# main-board.net
KiCad netlist of a schematic drawn in EAGLE
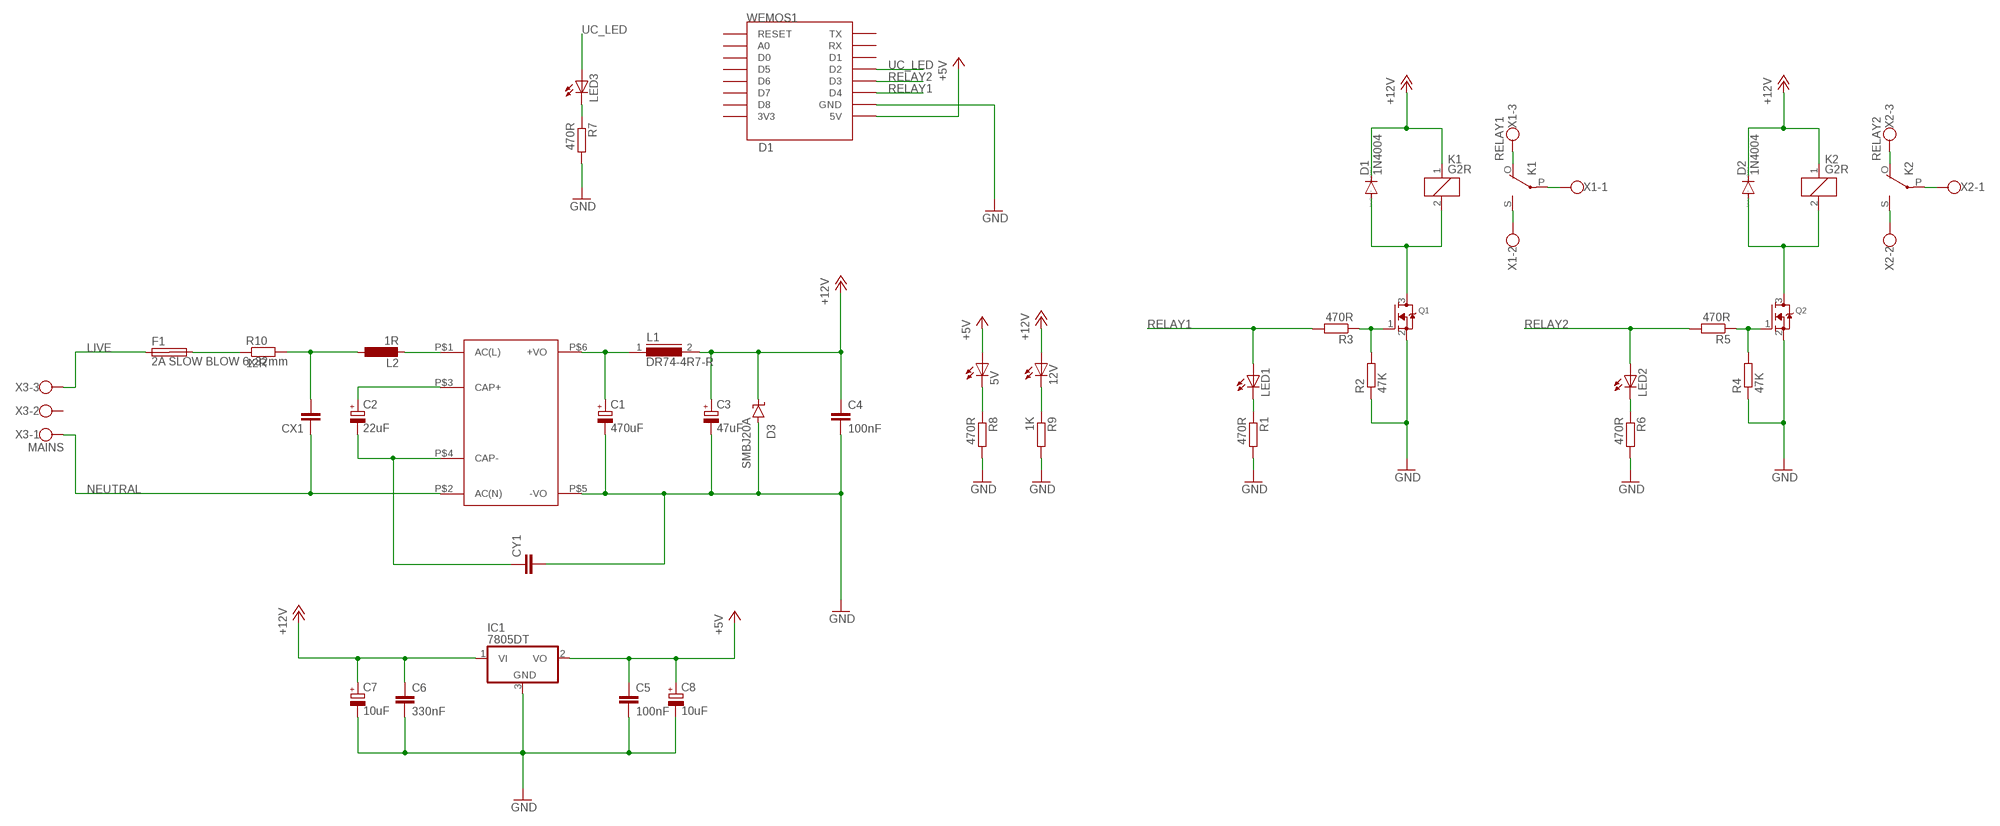
[diagram p0: schematic, sheet 1]

(export (version "E")
  (design (tool "Eeschema 10.0.6"))
  (components
    (comp (ref "5V")
      (value "LEDSMT1206")
      (footprint "eagle-import:1206")
      (libsource (lib "eagle-import") (part "LEDSMT1206"))
    )
    (comp (ref "12V")
      (value "LEDSMT1206")
      (footprint "eagle-import:1206")
      (libsource (lib "eagle-import") (part "LEDSMT1206"))
    )
    (comp (ref "C1")
      (value "470uF")
      (footprint "eagle-import:PANASONIC_E")
      (libsource (lib "eagle-import") (part "CPOL-EUE"))
    )
    (comp (ref "C2")
      (value "22uF")
      (footprint "eagle-import:E7,5-16")
      (libsource (lib "eagle-import") (part "CPOL-EUE7.5-16"))
    )
    (comp (ref "C3")
      (value "47uF")
      (footprint "eagle-import:PANASONIC_D")
      (libsource (lib "eagle-import") (part "CPOL-EUD"))
    )
    (comp (ref "C4")
      (value "100nF")
      (footprint "eagle-import:C0603")
      (libsource (lib "eagle-import") (part "C-EUC0603"))
    )
    (comp (ref "C5")
      (value "100nF")
      (footprint "eagle-import:C0603")
      (libsource (lib "eagle-import") (part "C-EUC0603"))
    )
    (comp (ref "C6")
      (value "330nF")
      (footprint "eagle-import:C0603")
      (libsource (lib "eagle-import") (part "C-EUC0603"))
    )
    (comp (ref "C7")
      (value "10uF")
      (footprint "eagle-import:PANASONIC_B")
      (libsource (lib "eagle-import") (part "CPOL-EUB"))
    )
    (comp (ref "C8")
      (value "10uF")
      (footprint "eagle-import:PANASONIC_B")
      (libsource (lib "eagle-import") (part "CPOL-EUB"))
    )
    (comp (ref "CX1")
      (value "CXXC15B8")
      (footprint "eagle-import:XC15B8")
      (libsource (lib "eagle-import") (part "CXXC15B8"))
    )
    (comp (ref "CY1")
      (value "CYYC10B5")
      (footprint "eagle-import:YC10B5")
      (libsource (lib "eagle-import") (part "CYYC10B5"))
    )
    (comp (ref "D1")
      (value "1N4004")
      (footprint "eagle-import:DO41-10")
      (libsource (lib "eagle-import") (part "1N4004"))
    )
    (comp (ref "D2")
      (value "1N4004")
      (footprint "eagle-import:DO41-10")
      (libsource (lib "eagle-import") (part "1N4004"))
    )
    (comp (ref "D3")
      (value "SMBJ20A")
      (footprint "eagle-import:SMBJ")
      (libsource (lib "eagle-import") (part "SUPPRESSOR-SMBJ"))
    )
    (comp (ref "F1")
      (value "2A SLOW BLOW 6x32mm")
      (footprint "eagle-import:SH32")
      (fields (field (name "MPN") "10207101009"))
      (libsource (lib "eagle-import") (part "SH32"))
    )
    (comp (ref "IC1")
      (value "7805DT")
      (footprint "eagle-import:TO252")
      (libsource (lib "eagle-import") (part "78DT05"))
    )
    (comp (ref "K1")
      (value "G2R")
      (footprint "eagle-import:G2R")
      (libsource (lib "eagle-import") (part "G2R"))
    )
    (comp (ref "K2")
      (value "G2R")
      (footprint "eagle-import:G2R")
      (libsource (lib "eagle-import") (part "G2R"))
    )
    (comp (ref "L1")
      (value "DR74-4R7-R")
      (footprint "eagle-import:DR74")
      (libsource (lib "eagle-import") (part "DR74"))
    )
    (comp (ref "L2")
      (value "1R")
      (footprint "eagle-import:6000-XXXX-RC")
      (libsource (lib "eagle-import") (part "L-EU6000-XXX-RC"))
    )
    (comp (ref "LED1")
      (value "LEDSMT1206")
      (footprint "eagle-import:1206")
      (libsource (lib "eagle-import") (part "LEDSMT1206"))
    )
    (comp (ref "LED2")
      (value "LEDSMT1206")
      (footprint "eagle-import:1206")
      (libsource (lib "eagle-import") (part "LEDSMT1206"))
    )
    (comp (ref "LED3")
      (value "LEDSMT1206")
      (footprint "eagle-import:1206")
      (libsource (lib "eagle-import") (part "LEDSMT1206"))
    )
    (comp (ref "Q1")
      (value "MOSFET-NREFLOW")
      (footprint "eagle-import:SOT23")
      (libsource (lib "eagle-import") (part "MOSFET-NREFLOW"))
    )
    (comp (ref "Q2")
      (value "MOSFET-NREFLOW")
      (footprint "eagle-import:SOT23")
      (libsource (lib "eagle-import") (part "MOSFET-NREFLOW"))
    )
    (comp (ref "R1")
      (value "470R")
      (footprint "eagle-import:R0603")
      (libsource (lib "eagle-import") (part "R-EU_R0603"))
    )
    (comp (ref "R2")
      (value "47K")
      (footprint "eagle-import:R0603")
      (libsource (lib "eagle-import") (part "R-EU_R0603"))
    )
    (comp (ref "R3")
      (value "470R")
      (footprint "eagle-import:R0603")
      (libsource (lib "eagle-import") (part "R-EU_R0603"))
    )
    (comp (ref "R4")
      (value "47K")
      (footprint "eagle-import:R0603")
      (libsource (lib "eagle-import") (part "R-EU_R0603"))
    )
    (comp (ref "R5")
      (value "470R")
      (footprint "eagle-import:R0603")
      (libsource (lib "eagle-import") (part "R-EU_R0603"))
    )
    (comp (ref "R6")
      (value "470R")
      (footprint "eagle-import:R0603")
      (libsource (lib "eagle-import") (part "R-EU_R0603"))
    )
    (comp (ref "R7")
      (value "470R")
      (footprint "eagle-import:R0603")
      (libsource (lib "eagle-import") (part "R-EU_R0603"))
    )
    (comp (ref "R8")
      (value "470R")
      (footprint "eagle-import:R0603")
      (libsource (lib "eagle-import") (part "R-EU_R0603"))
    )
    (comp (ref "R9")
      (value "1K")
      (footprint "eagle-import:R0603")
      (libsource (lib "eagle-import") (part "R-EU_R0603"))
    )
    (comp (ref "R10")
      (value "12R")
      (footprint "eagle-import:0922V")
      (libsource (lib "eagle-import") (part "R-EU_0922V"))
    )
    (comp (ref "U$1")
      (value "MP-LS05")
      (footprint "eagle-import:MP-LS05")
      (libsource (lib "eagle-import") (part "MP-LS05"))
    )
    (comp (ref "WEMOS1")
      (value "D1")
      (footprint "eagle-import:WEMOS-D1-MINI")
      (libsource (lib "eagle-import") (part "WEMOS-D1-MINI"))
    )
    (comp (ref "X1")
      (value "RELAY1")
      (footprint "eagle-import:W237-103")
      (fields (field (name "MPN") "237-103"))
      (libsource (lib "eagle-import") (part "W237-103"))
    )
    (comp (ref "X2")
      (value "RELAY2")
      (footprint "eagle-import:W237-103")
      (fields (field (name "MPN") "237-103"))
      (libsource (lib "eagle-import") (part "W237-103"))
    )
    (comp (ref "X3")
      (value "MAINS")
      (footprint "eagle-import:W237-103")
      (fields (field (name "MPN") "237-103"))
      (libsource (lib "eagle-import") (part "W237-103"))
    )
  )
  (nets
    (net (code "1") (name "+5V") (class "Default")
      (node (ref "5V") (pin "A") (pinfunction "A_A") (pintype "passive"))
      (node (ref "C5") (pin "1") (pinfunction "1_1") (pintype "passive"))
      (node (ref "C8") (pin "+") (pinfunction "+_+") (pintype "passive"))
      (node (ref "IC1") (pin "2") (pinfunction "VO_2") (pintype "passive"))
      (node (ref "WEMOS1") (pin "5V") (pinfunction "5V_5V") (pintype "bidirectional"))
    )
    (net (code "2") (name "+12V") (class "Default")
      (node (ref "12V") (pin "A") (pinfunction "A_A") (pintype "passive"))
      (node (ref "C3") (pin "+") (pinfunction "+_+") (pintype "passive"))
      (node (ref "C4") (pin "1") (pinfunction "1_1") (pintype "passive"))
      (node (ref "C6") (pin "1") (pinfunction "1_1") (pintype "passive"))
      (node (ref "C7") (pin "+") (pinfunction "+_+") (pintype "passive"))
      (node (ref "D1") (pin "C") (pinfunction "C_C") (pintype "passive"))
      (node (ref "D2") (pin "C") (pinfunction "C_C") (pintype "passive"))
      (node (ref "D3") (pin "C") (pinfunction "C_C") (pintype "passive"))
      (node (ref "IC1") (pin "1") (pinfunction "VI_1") (pintype "input"))
      (node (ref "K1") (pin "1") (pinfunction "1_1") (pintype "passive"))
      (node (ref "K2") (pin "1") (pinfunction "1_1") (pintype "passive"))
      (node (ref "L1") (pin "2") (pinfunction "2_2") (pintype "passive"))
    )
    (net (code "3") (name "/LIVE") (class "Default")
      (node (ref "F1") (pin "1A") (pinfunction "1A_1A") (pintype "passive"))
      (node (ref "X3") (pin "3") (pinfunction "KL_3") (pintype "passive"))
    )
    (net (code "4") (name "/NEUTRAL") (class "Default")
      (node (ref "CX1") (pin "1") (pinfunction "1_1") (pintype "passive"))
      (node (ref "U$1") (pin "P$2") (pinfunction "AC(N)_P$2") (pintype "bidirectional"))
      (node (ref "X3") (pin "1") (pinfunction "KL_1") (pintype "passive"))
    )
    (net (code "5") (name "/RELAY1") (class "Default")
      (node (ref "LED1") (pin "A") (pinfunction "A_A") (pintype "passive"))
      (node (ref "R3") (pin "2") (pinfunction "2_2") (pintype "passive"))
      (node (ref "WEMOS1") (pin "D4") (pinfunction "D4_D4") (pintype "bidirectional"))
    )
    (net (code "6") (name "/RELAY2") (class "Default")
      (node (ref "LED2") (pin "A") (pinfunction "A_A") (pintype "passive"))
      (node (ref "R5") (pin "2") (pinfunction "2_2") (pintype "passive"))
      (node (ref "WEMOS1") (pin "D3") (pinfunction "D3_D3") (pintype "bidirectional"))
    )
    (net (code "7") (name "/UC_LED") (class "Default")
      (node (ref "LED3") (pin "A") (pinfunction "A_A") (pintype "passive"))
      (node (ref "WEMOS1") (pin "D2") (pinfunction "D2_D2") (pintype "bidirectional"))
    )
    (net (code "8") (name "GND") (class "Default")
      (node (ref "C1") (pin "-") (pinfunction "-_-") (pintype "passive"))
      (node (ref "C3") (pin "-") (pinfunction "-_-") (pintype "passive"))
      (node (ref "C4") (pin "2") (pinfunction "2_2") (pintype "passive"))
      (node (ref "C5") (pin "2") (pinfunction "2_2") (pintype "passive"))
      (node (ref "C6") (pin "2") (pinfunction "2_2") (pintype "passive"))
      (node (ref "C7") (pin "-") (pinfunction "-_-") (pintype "passive"))
      (node (ref "C8") (pin "-") (pinfunction "-_-") (pintype "passive"))
      (node (ref "CY1") (pin "2") (pinfunction "2_2") (pintype "passive"))
      (node (ref "D3") (pin "A") (pinfunction "A_A") (pintype "passive"))
      (node (ref "IC1") (pin "3") (pinfunction "GND_3") (pintype "passive"))
      (node (ref "Q1") (pin "2") (pinfunction "S_2") (pintype "bidirectional"))
      (node (ref "Q2") (pin "2") (pinfunction "S_2") (pintype "bidirectional"))
      (node (ref "R1") (pin "2") (pinfunction "2_2") (pintype "passive"))
      (node (ref "R2") (pin "1") (pinfunction "1_1") (pintype "passive"))
      (node (ref "R4") (pin "1") (pinfunction "1_1") (pintype "passive"))
      (node (ref "R6") (pin "2") (pinfunction "2_2") (pintype "passive"))
      (node (ref "R7") (pin "2") (pinfunction "2_2") (pintype "passive"))
      (node (ref "R8") (pin "2") (pinfunction "2_2") (pintype "passive"))
      (node (ref "R9") (pin "2") (pinfunction "2_2") (pintype "passive"))
      (node (ref "U$1") (pin "P$5") (pinfunction "-VO_P$5") (pintype "bidirectional"))
      (node (ref "WEMOS1") (pin "GND") (pinfunction "GND_GND") (pintype "bidirectional"))
    )
    (net (code "9") (name "Net-(5V-PadC)") (class "Default")
      (node (ref "5V") (pin "C") (pinfunction "C_C") (pintype "passive"))
      (node (ref "R8") (pin "1") (pinfunction "1_1") (pintype "passive"))
    )
    (net (code "10") (name "Net-(12V-PadC)") (class "Default")
      (node (ref "12V") (pin "C") (pinfunction "C_C") (pintype "passive"))
      (node (ref "R9") (pin "1") (pinfunction "1_1") (pintype "passive"))
    )
    (net (code "11") (name "Net-(CX1-Pad2)") (class "Default")
      (node (ref "CX1") (pin "2") (pinfunction "2_2") (pintype "passive"))
      (node (ref "L2") (pin "1") (pinfunction "1_1") (pintype "passive"))
      (node (ref "R10") (pin "2") (pinfunction "2_2") (pintype "passive"))
    )
    (net (code "12") (name "Net-(F1-Pad2A)") (class "Default")
      (node (ref "F1") (pin "2A") (pinfunction "2A_2A") (pintype "passive"))
      (node (ref "R10") (pin "1") (pinfunction "1_1") (pintype "passive"))
    )
    (net (code "13") (name "Net-(LED1-PadC)") (class "Default")
      (node (ref "LED1") (pin "C") (pinfunction "C_C") (pintype "passive"))
      (node (ref "R1") (pin "1") (pinfunction "1_1") (pintype "passive"))
    )
    (net (code "14") (name "Net-(LED2-PadC)") (class "Default")
      (node (ref "LED2") (pin "C") (pinfunction "C_C") (pintype "passive"))
      (node (ref "R6") (pin "1") (pinfunction "1_1") (pintype "passive"))
    )
    (net (code "15") (name "Net-(LED3-PadC)") (class "Default")
      (node (ref "LED3") (pin "C") (pinfunction "C_C") (pintype "passive"))
      (node (ref "R7") (pin "1") (pinfunction "1_1") (pintype "passive"))
    )
    (net (code "16") (name "Net-(Q1-D)") (class "Default")
      (node (ref "D1") (pin "A") (pinfunction "A_A") (pintype "passive"))
      (node (ref "K1") (pin "2") (pinfunction "2_2") (pintype "passive"))
      (node (ref "Q1") (pin "3") (pinfunction "D_3") (pintype "bidirectional"))
    )
    (net (code "17") (name "Net-(Q1-G)") (class "Default")
      (node (ref "Q1") (pin "1") (pinfunction "G_1") (pintype "bidirectional"))
      (node (ref "R2") (pin "2") (pinfunction "2_2") (pintype "passive"))
      (node (ref "R3") (pin "1") (pinfunction "1_1") (pintype "passive"))
    )
    (net (code "18") (name "Net-(Q2-D)") (class "Default")
      (node (ref "D2") (pin "A") (pinfunction "A_A") (pintype "passive"))
      (node (ref "K2") (pin "2") (pinfunction "2_2") (pintype "passive"))
      (node (ref "Q2") (pin "3") (pinfunction "D_3") (pintype "bidirectional"))
    )
    (net (code "19") (name "Net-(Q2-G)") (class "Default")
      (node (ref "Q2") (pin "1") (pinfunction "G_1") (pintype "bidirectional"))
      (node (ref "R4") (pin "2") (pinfunction "2_2") (pintype "passive"))
      (node (ref "R5") (pin "1") (pinfunction "1_1") (pintype "passive"))
    )
    (net (code "20") (name "Net-(U$1-+VO)") (class "Default")
      (node (ref "C1") (pin "+") (pinfunction "+_+") (pintype "passive"))
      (node (ref "L1") (pin "1") (pinfunction "1_1") (pintype "passive"))
      (node (ref "U$1") (pin "P$6") (pinfunction "+VO_P$6") (pintype "bidirectional"))
    )
    (net (code "21") (name "Net-(U$1-AC(L))") (class "Default")
      (node (ref "L2") (pin "2") (pinfunction "2_2") (pintype "passive"))
      (node (ref "U$1") (pin "P$1") (pinfunction "AC(L)_P$1") (pintype "bidirectional"))
    )
    (net (code "22") (name "Net-(U$1-CAP+)") (class "Default")
      (node (ref "C2") (pin "+") (pinfunction "+_+") (pintype "passive"))
      (node (ref "U$1") (pin "P$3") (pinfunction "CAP+_P$3") (pintype "bidirectional"))
    )
    (net (code "23") (name "Net-(U$1-CAP-)") (class "Default")
      (node (ref "C2") (pin "-") (pinfunction "-_-") (pintype "passive"))
      (node (ref "CY1") (pin "1") (pinfunction "1_1") (pintype "passive"))
      (node (ref "U$1") (pin "P$4") (pinfunction "CAP-_P$4") (pintype "bidirectional"))
    )
    (net (code "24") (name "Net-(X1A-KL)") (class "Default")
      (node (ref "K1") (pin "P") (pinfunction "P_P") (pintype "passive"))
      (node (ref "X1") (pin "1") (pinfunction "KL_1") (pintype "passive"))
    )
    (net (code "25") (name "Net-(X1B-KL)") (class "Default")
      (node (ref "K1") (pin "S") (pinfunction "S_S") (pintype "passive"))
      (node (ref "X1") (pin "2") (pinfunction "KL_2") (pintype "passive"))
    )
    (net (code "26") (name "Net-(X1C-KL)") (class "Default")
      (node (ref "K1") (pin "O") (pinfunction "O_O") (pintype "passive"))
      (node (ref "X1") (pin "3") (pinfunction "KL_3") (pintype "passive"))
    )
    (net (code "27") (name "Net-(X2A-KL)") (class "Default")
      (node (ref "K2") (pin "P") (pinfunction "P_P") (pintype "passive"))
      (node (ref "X2") (pin "1") (pinfunction "KL_1") (pintype "passive"))
    )
    (net (code "28") (name "Net-(X2B-KL)") (class "Default")
      (node (ref "K2") (pin "S") (pinfunction "S_S") (pintype "passive"))
      (node (ref "X2") (pin "2") (pinfunction "KL_2") (pintype "passive"))
    )
    (net (code "29") (name "Net-(X2C-KL)") (class "Default")
      (node (ref "K2") (pin "O") (pinfunction "O_O") (pintype "passive"))
      (node (ref "X2") (pin "3") (pinfunction "KL_3") (pintype "passive"))
    )
    (net (code "30") (name "unconnected-(F1-Pad1B)") (class "Default")
      (node (ref "F1") (pin "1B") (pinfunction "1B_1B") (pintype "passive"))
    )
    (net (code "31") (name "unconnected-(F1-Pad2B)") (class "Default")
      (node (ref "F1") (pin "2B") (pinfunction "2B_2B") (pintype "passive"))
    )
    (net (code "32") (name "unconnected-(WEMOS1-Pad3V3)") (class "Default")
      (node (ref "WEMOS1") (pin "3V3") (pinfunction "3V3_3V3") (pintype "bidirectional"))
    )
    (net (code "33") (name "unconnected-(WEMOS1-PadA0)") (class "Default")
      (node (ref "WEMOS1") (pin "A0") (pinfunction "A0_A0") (pintype "bidirectional"))
    )
    (net (code "34") (name "unconnected-(WEMOS1-PadD0)") (class "Default")
      (node (ref "WEMOS1") (pin "D0") (pinfunction "D0_D0") (pintype "bidirectional"))
    )
    (net (code "35") (name "unconnected-(WEMOS1-PadD1)") (class "Default")
      (node (ref "WEMOS1") (pin "D1") (pinfunction "D1_D1") (pintype "bidirectional"))
    )
    (net (code "36") (name "unconnected-(WEMOS1-PadD5)") (class "Default")
      (node (ref "WEMOS1") (pin "D5") (pinfunction "D5_D5") (pintype "bidirectional"))
    )
    (net (code "37") (name "unconnected-(WEMOS1-PadD6)") (class "Default")
      (node (ref "WEMOS1") (pin "D6") (pinfunction "D6_D6") (pintype "bidirectional"))
    )
    (net (code "38") (name "unconnected-(WEMOS1-PadD7)") (class "Default")
      (node (ref "WEMOS1") (pin "D7") (pinfunction "D7_D7") (pintype "bidirectional"))
    )
    (net (code "39") (name "unconnected-(WEMOS1-PadD8)") (class "Default")
      (node (ref "WEMOS1") (pin "D8") (pinfunction "D8_D8") (pintype "bidirectional"))
    )
    (net (code "40") (name "unconnected-(WEMOS1-PadRESET)") (class "Default")
      (node (ref "WEMOS1") (pin "RESET") (pinfunction "RESET_RESET") (pintype "bidirectional"))
    )
    (net (code "41") (name "unconnected-(WEMOS1-PadRX)") (class "Default")
      (node (ref "WEMOS1") (pin "RX") (pinfunction "RX_RX") (pintype "bidirectional"))
    )
    (net (code "42") (name "unconnected-(WEMOS1-PadTX)") (class "Default")
      (node (ref "WEMOS1") (pin "TX") (pinfunction "TX_TX") (pintype "bidirectional"))
    )
    (net (code "43") (name "unconnected-(X3B-KL-Pad2)") (class "Default")
      (node (ref "X3") (pin "2") (pinfunction "KL_2") (pintype "passive"))
    )
  )
)
